# rtkSchematic.net
KiCad netlist of a schematic drawn in EAGLE
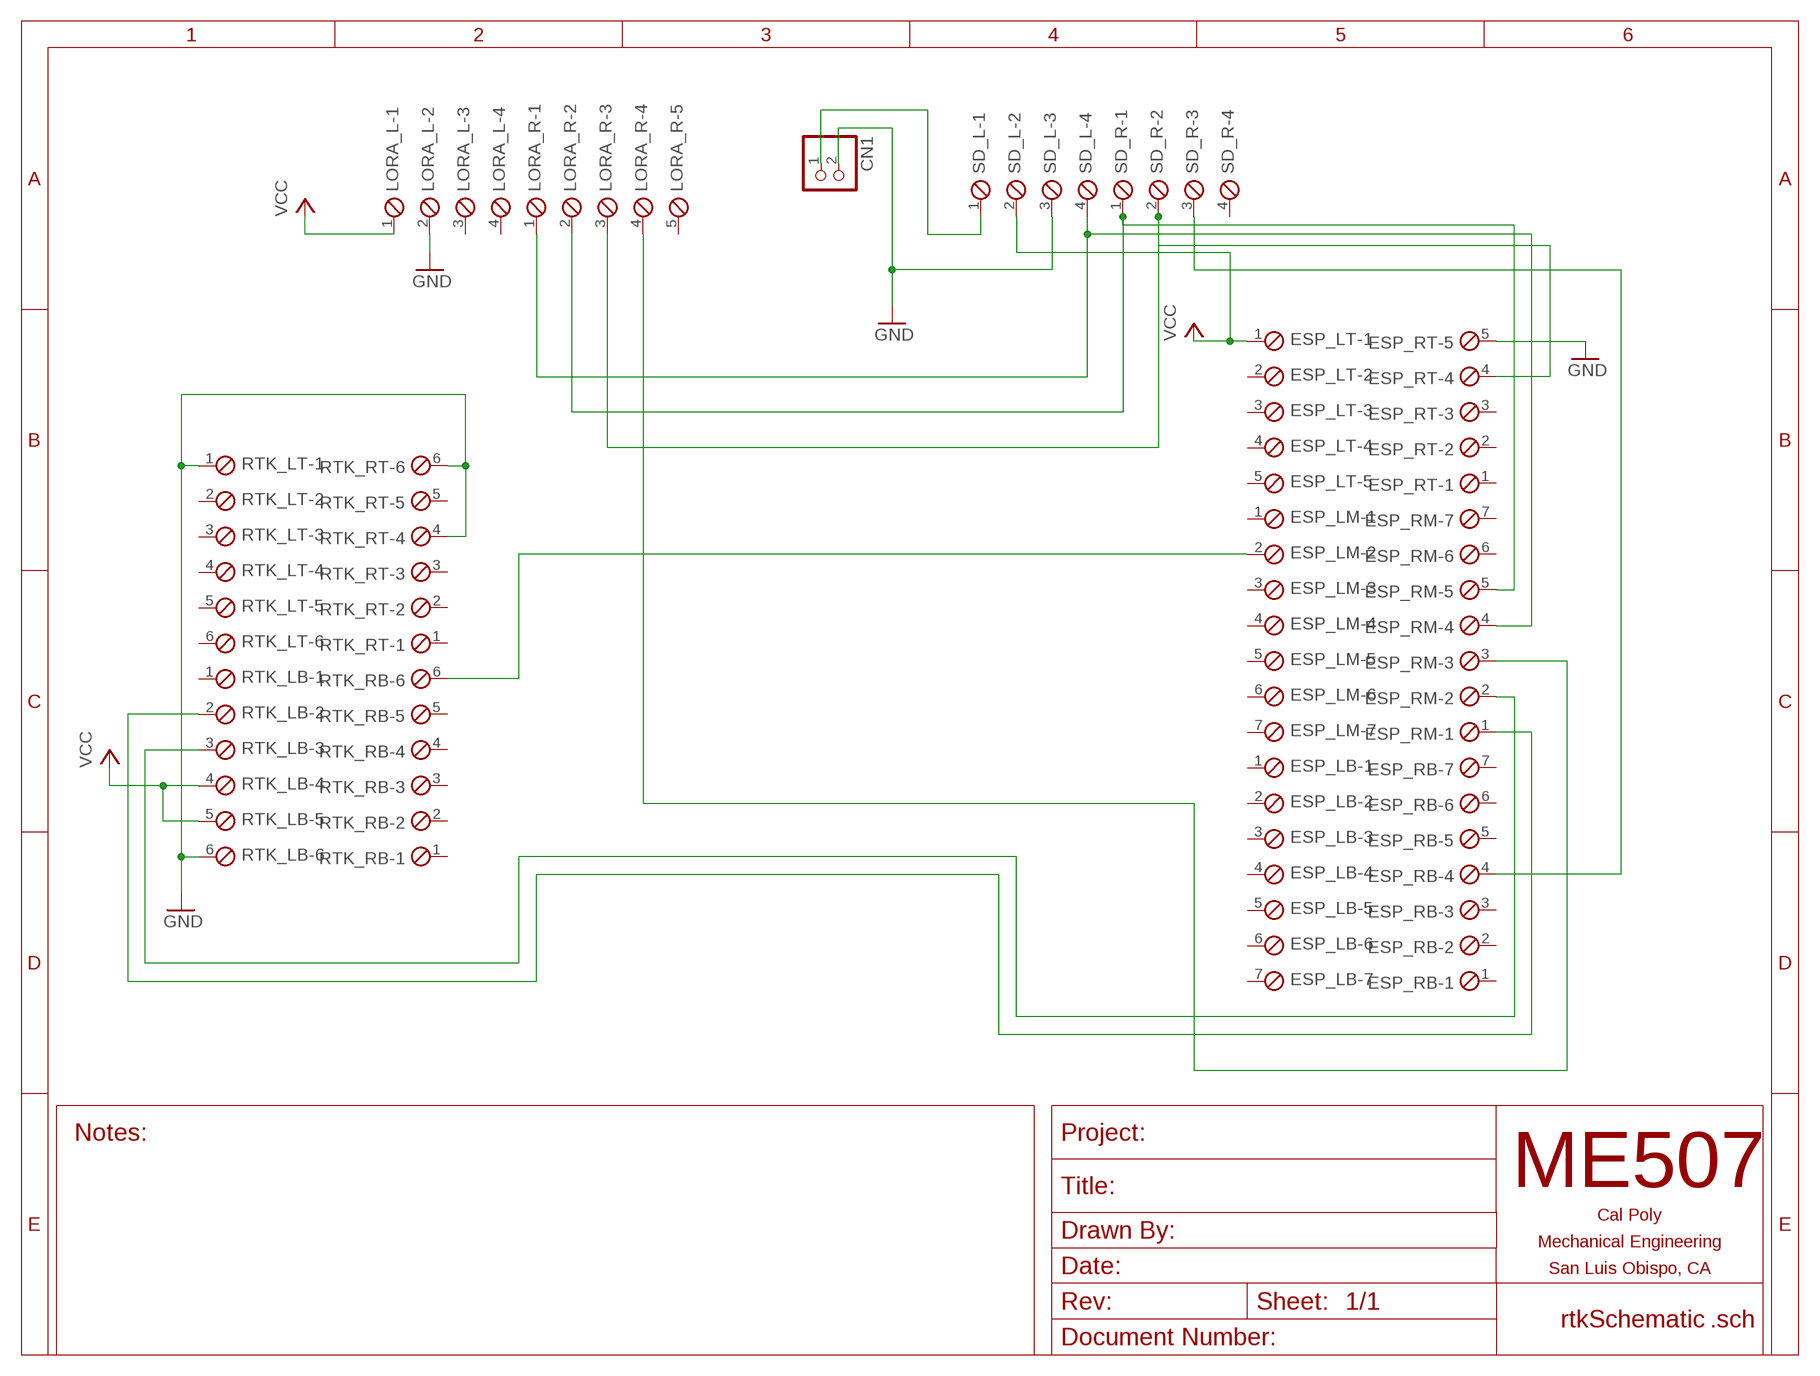
[diagram p0: schematic, sheet 1]

(export (version "E")
  (design (tool "Eeschema 10.0.6"))
  (components
    (comp (ref "CN1")
      (value "JST_2PIN-SMT-RA")
      (footprint "eagle-import:JST-PH-2-SMT-RA")
      (libsource (lib "eagle-import") (part "JST_2PIN-SMT-RA"))
    )
    (comp (ref "ESP_LB")
      (value "SCREWTERM_7P_254")
      (footprint "eagle-import:7POL254")
      (libsource (lib "eagle-import") (part "SCREWTERM_7P_254"))
    )
    (comp (ref "ESP_LM")
      (value "SCREWTERM_7P_254")
      (footprint "eagle-import:7POL254")
      (libsource (lib "eagle-import") (part "SCREWTERM_7P_254"))
    )
    (comp (ref "ESP_LT")
      (value "SCREWTERM_5P_254")
      (footprint "eagle-import:5POL254")
      (libsource (lib "eagle-import") (part "SCREWTERM_5P_254"))
    )
    (comp (ref "ESP_RB")
      (value "SCREWTERM_7P_254")
      (footprint "eagle-import:7POL254")
      (libsource (lib "eagle-import") (part "SCREWTERM_7P_254"))
    )
    (comp (ref "ESP_RM")
      (value "SCREWTERM_7P_254")
      (footprint "eagle-import:7POL254")
      (libsource (lib "eagle-import") (part "SCREWTERM_7P_254"))
    )
    (comp (ref "ESP_RT")
      (value "SCREWTERM_5P_254")
      (footprint "eagle-import:5POL254")
      (libsource (lib "eagle-import") (part "SCREWTERM_5P_254"))
    )
    (comp (ref "LORA_L")
      (value "SCREWTERM_4P_254")
      (footprint "eagle-import:4POL254")
      (libsource (lib "eagle-import") (part "SCREWTERM_4P_254"))
    )
    (comp (ref "LORA_R")
      (value "SCREWTERM_5P_254")
      (footprint "eagle-import:5POL254")
      (libsource (lib "eagle-import") (part "SCREWTERM_5P_254"))
    )
    (comp (ref "RTK_LB")
      (value "SCREWTERM_6P_254")
      (footprint "eagle-import:6POL254")
      (libsource (lib "eagle-import") (part "SCREWTERM_6P_254"))
    )
    (comp (ref "RTK_LT")
      (value "SCREWTERM_6P_254")
      (footprint "eagle-import:6POL254")
      (libsource (lib "eagle-import") (part "SCREWTERM_6P_254"))
    )
    (comp (ref "RTK_RB")
      (value "SCREWTERM_6P_254")
      (footprint "eagle-import:6POL254")
      (libsource (lib "eagle-import") (part "SCREWTERM_6P_254"))
    )
    (comp (ref "RTK_RT")
      (value "SCREWTERM_6P_254")
      (footprint "eagle-import:6POL254")
      (libsource (lib "eagle-import") (part "SCREWTERM_6P_254"))
    )
    (comp (ref "SD_L")
      (value "SCREWTERM_4P_254")
      (footprint "eagle-import:4POL254")
      (libsource (lib "eagle-import") (part "SCREWTERM_4P_254"))
    )
    (comp (ref "SD_R")
      (value "SCREWTERM_4P_254")
      (footprint "eagle-import:4POL254")
      (libsource (lib "eagle-import") (part "SCREWTERM_4P_254"))
    )
  )
  (nets
    (net (code "1") (name "GND") (class "Default")
      (node (ref "CN1") (pin "2") (pinfunction "1_2") (pintype "passive"))
      (node (ref "ESP_RT") (pin "5") (pinfunction "1_5") (pintype "passive"))
      (node (ref "LORA_L") (pin "2") (pinfunction "1_2") (pintype "passive"))
      (node (ref "RTK_LB") (pin "6") (pinfunction "1_6") (pintype "passive"))
      (node (ref "RTK_LT") (pin "1") (pinfunction "1_1") (pintype "passive"))
      (node (ref "RTK_RT") (pin "4") (pinfunction "1_4") (pintype "passive"))
      (node (ref "RTK_RT") (pin "6") (pinfunction "1_6") (pintype "passive"))
      (node (ref "SD_L") (pin "3") (pinfunction "1_3") (pintype "passive"))
    )
    (net (code "2") (name "Net-(CN1-2)") (class "Default")
      (node (ref "CN1") (pin "1") (pinfunction "2_1") (pintype "passive"))
      (node (ref "SD_L") (pin "1") (pinfunction "1_1") (pintype "passive"))
    )
    (net (code "3") (name "Net-(ESP_LMB-1)") (class "Default")
      (node (ref "ESP_LM") (pin "2") (pinfunction "1_2") (pintype "passive"))
      (node (ref "RTK_RB") (pin "6") (pinfunction "1_6") (pintype "passive"))
    )
    (net (code "4") (name "Net-(ESP_RBD-1)") (class "Default")
      (node (ref "ESP_RB") (pin "4") (pinfunction "1_4") (pintype "passive"))
      (node (ref "SD_R") (pin "3") (pinfunction "1_3") (pintype "passive"))
    )
    (net (code "5") (name "Net-(ESP_RMB-1)") (class "Default")
      (node (ref "ESP_RM") (pin "2") (pinfunction "1_2") (pintype "passive"))
      (node (ref "RTK_LB") (pin "3") (pinfunction "1_3") (pintype "passive"))
    )
    (net (code "6") (name "Net-(ESP_RMC-1)") (class "Default")
      (node (ref "ESP_RM") (pin "3") (pinfunction "1_3") (pintype "passive"))
      (node (ref "LORA_R") (pin "4") (pinfunction "1_4") (pintype "passive"))
    )
    (net (code "7") (name "Net-(ESP_RMD-1)") (class "Default")
      (node (ref "ESP_RM") (pin "4") (pinfunction "1_4") (pintype "passive"))
      (node (ref "LORA_R") (pin "1") (pinfunction "1_1") (pintype "passive"))
      (node (ref "SD_L") (pin "4") (pinfunction "1_4") (pintype "passive"))
    )
    (net (code "8") (name "Net-(ESP_RME-1)") (class "Default")
      (node (ref "ESP_RM") (pin "5") (pinfunction "1_5") (pintype "passive"))
      (node (ref "LORA_R") (pin "2") (pinfunction "1_2") (pintype "passive"))
      (node (ref "SD_R") (pin "1") (pinfunction "1_1") (pintype "passive"))
    )
    (net (code "9") (name "Net-(ESP_RTD-1)") (class "Default")
      (node (ref "ESP_RT") (pin "4") (pinfunction "1_4") (pintype "passive"))
      (node (ref "LORA_R") (pin "3") (pinfunction "1_3") (pintype "passive"))
      (node (ref "SD_R") (pin "2") (pinfunction "1_2") (pintype "passive"))
    )
    (net (code "10") (name "Net-(RTK_LBB-1)") (class "Default")
      (node (ref "ESP_RM") (pin "1") (pinfunction "1_1") (pintype "passive"))
      (node (ref "RTK_LB") (pin "2") (pinfunction "1_2") (pintype "passive"))
    )
    (net (code "11") (name "VCC") (class "Default")
      (node (ref "ESP_LT") (pin "1") (pinfunction "1_1") (pintype "passive"))
      (node (ref "LORA_L") (pin "1") (pinfunction "1_1") (pintype "passive"))
      (node (ref "RTK_LB") (pin "4") (pinfunction "1_4") (pintype "passive"))
      (node (ref "RTK_LB") (pin "5") (pinfunction "1_5") (pintype "passive"))
      (node (ref "SD_L") (pin "2") (pinfunction "1_2") (pintype "passive"))
    )
    (net (code "12") (name "unconnected-(ESP_LB-Pad1)") (class "Default")
      (node (ref "ESP_LB") (pin "1") (pinfunction "1_1") (pintype "passive"))
    )
    (net (code "13") (name "unconnected-(ESP_LBB-1-Pad2)") (class "Default")
      (node (ref "ESP_LB") (pin "2") (pinfunction "1_2") (pintype "passive"))
    )
    (net (code "14") (name "unconnected-(ESP_LBC-1-Pad3)") (class "Default")
      (node (ref "ESP_LB") (pin "3") (pinfunction "1_3") (pintype "passive"))
    )
    (net (code "15") (name "unconnected-(ESP_LBD-1-Pad4)") (class "Default")
      (node (ref "ESP_LB") (pin "4") (pinfunction "1_4") (pintype "passive"))
    )
    (net (code "16") (name "unconnected-(ESP_LBE-1-Pad5)") (class "Default")
      (node (ref "ESP_LB") (pin "5") (pinfunction "1_5") (pintype "passive"))
    )
    (net (code "17") (name "unconnected-(ESP_LBF-1-Pad6)") (class "Default")
      (node (ref "ESP_LB") (pin "6") (pinfunction "1_6") (pintype "passive"))
    )
    (net (code "18") (name "unconnected-(ESP_LBG-1-Pad7)") (class "Default")
      (node (ref "ESP_LB") (pin "7") (pinfunction "1_7") (pintype "passive"))
    )
    (net (code "19") (name "unconnected-(ESP_LM-Pad1)") (class "Default")
      (node (ref "ESP_LM") (pin "1") (pinfunction "1_1") (pintype "passive"))
    )
    (net (code "20") (name "unconnected-(ESP_LMC-1-Pad3)") (class "Default")
      (node (ref "ESP_LM") (pin "3") (pinfunction "1_3") (pintype "passive"))
    )
    (net (code "21") (name "unconnected-(ESP_LMD-1-Pad4)") (class "Default")
      (node (ref "ESP_LM") (pin "4") (pinfunction "1_4") (pintype "passive"))
    )
    (net (code "22") (name "unconnected-(ESP_LME-1-Pad5)") (class "Default")
      (node (ref "ESP_LM") (pin "5") (pinfunction "1_5") (pintype "passive"))
    )
    (net (code "23") (name "unconnected-(ESP_LMF-1-Pad6)") (class "Default")
      (node (ref "ESP_LM") (pin "6") (pinfunction "1_6") (pintype "passive"))
    )
    (net (code "24") (name "unconnected-(ESP_LMG-1-Pad7)") (class "Default")
      (node (ref "ESP_LM") (pin "7") (pinfunction "1_7") (pintype "passive"))
    )
    (net (code "25") (name "unconnected-(ESP_LTB-1-Pad2)") (class "Default")
      (node (ref "ESP_LT") (pin "2") (pinfunction "1_2") (pintype "passive"))
    )
    (net (code "26") (name "unconnected-(ESP_LTC-1-Pad3)") (class "Default")
      (node (ref "ESP_LT") (pin "3") (pinfunction "1_3") (pintype "passive"))
    )
    (net (code "27") (name "unconnected-(ESP_LTD-1-Pad4)") (class "Default")
      (node (ref "ESP_LT") (pin "4") (pinfunction "1_4") (pintype "passive"))
    )
    (net (code "28") (name "unconnected-(ESP_LTE-1-Pad5)") (class "Default")
      (node (ref "ESP_LT") (pin "5") (pinfunction "1_5") (pintype "passive"))
    )
    (net (code "29") (name "unconnected-(ESP_RB-Pad1)") (class "Default")
      (node (ref "ESP_RB") (pin "1") (pinfunction "1_1") (pintype "passive"))
    )
    (net (code "30") (name "unconnected-(ESP_RBB-1-Pad2)") (class "Default")
      (node (ref "ESP_RB") (pin "2") (pinfunction "1_2") (pintype "passive"))
    )
    (net (code "31") (name "unconnected-(ESP_RBC-1-Pad3)") (class "Default")
      (node (ref "ESP_RB") (pin "3") (pinfunction "1_3") (pintype "passive"))
    )
    (net (code "32") (name "unconnected-(ESP_RBE-1-Pad5)") (class "Default")
      (node (ref "ESP_RB") (pin "5") (pinfunction "1_5") (pintype "passive"))
    )
    (net (code "33") (name "unconnected-(ESP_RBF-1-Pad6)") (class "Default")
      (node (ref "ESP_RB") (pin "6") (pinfunction "1_6") (pintype "passive"))
    )
    (net (code "34") (name "unconnected-(ESP_RBG-1-Pad7)") (class "Default")
      (node (ref "ESP_RB") (pin "7") (pinfunction "1_7") (pintype "passive"))
    )
    (net (code "35") (name "unconnected-(ESP_RMF-1-Pad6)") (class "Default")
      (node (ref "ESP_RM") (pin "6") (pinfunction "1_6") (pintype "passive"))
    )
    (net (code "36") (name "unconnected-(ESP_RMG-1-Pad7)") (class "Default")
      (node (ref "ESP_RM") (pin "7") (pinfunction "1_7") (pintype "passive"))
    )
    (net (code "37") (name "unconnected-(ESP_RT-Pad1)") (class "Default")
      (node (ref "ESP_RT") (pin "1") (pinfunction "1_1") (pintype "passive"))
    )
    (net (code "38") (name "unconnected-(ESP_RTB-1-Pad2)") (class "Default")
      (node (ref "ESP_RT") (pin "2") (pinfunction "1_2") (pintype "passive"))
    )
    (net (code "39") (name "unconnected-(ESP_RTC-1-Pad3)") (class "Default")
      (node (ref "ESP_RT") (pin "3") (pinfunction "1_3") (pintype "passive"))
    )
    (net (code "40") (name "unconnected-(LORA_LC-1-Pad3)") (class "Default")
      (node (ref "LORA_L") (pin "3") (pinfunction "1_3") (pintype "passive"))
    )
    (net (code "41") (name "unconnected-(LORA_LD-1-Pad4)") (class "Default")
      (node (ref "LORA_L") (pin "4") (pinfunction "1_4") (pintype "passive"))
    )
    (net (code "42") (name "unconnected-(LORA_RE-1-Pad5)") (class "Default")
      (node (ref "LORA_R") (pin "5") (pinfunction "1_5") (pintype "passive"))
    )
    (net (code "43") (name "unconnected-(RTK_LB-Pad1)") (class "Default")
      (node (ref "RTK_LB") (pin "1") (pinfunction "1_1") (pintype "passive"))
    )
    (net (code "44") (name "unconnected-(RTK_LTB-1-Pad2)") (class "Default")
      (node (ref "RTK_LT") (pin "2") (pinfunction "1_2") (pintype "passive"))
    )
    (net (code "45") (name "unconnected-(RTK_LTC-1-Pad3)") (class "Default")
      (node (ref "RTK_LT") (pin "3") (pinfunction "1_3") (pintype "passive"))
    )
    (net (code "46") (name "unconnected-(RTK_LTD-1-Pad4)") (class "Default")
      (node (ref "RTK_LT") (pin "4") (pinfunction "1_4") (pintype "passive"))
    )
    (net (code "47") (name "unconnected-(RTK_LTE-1-Pad5)") (class "Default")
      (node (ref "RTK_LT") (pin "5") (pinfunction "1_5") (pintype "passive"))
    )
    (net (code "48") (name "unconnected-(RTK_LTF-1-Pad6)") (class "Default")
      (node (ref "RTK_LT") (pin "6") (pinfunction "1_6") (pintype "passive"))
    )
    (net (code "49") (name "unconnected-(RTK_RB-Pad1)") (class "Default")
      (node (ref "RTK_RB") (pin "1") (pinfunction "1_1") (pintype "passive"))
    )
    (net (code "50") (name "unconnected-(RTK_RBB-1-Pad2)") (class "Default")
      (node (ref "RTK_RB") (pin "2") (pinfunction "1_2") (pintype "passive"))
    )
    (net (code "51") (name "unconnected-(RTK_RBC-1-Pad3)") (class "Default")
      (node (ref "RTK_RB") (pin "3") (pinfunction "1_3") (pintype "passive"))
    )
    (net (code "52") (name "unconnected-(RTK_RBD-1-Pad4)") (class "Default")
      (node (ref "RTK_RB") (pin "4") (pinfunction "1_4") (pintype "passive"))
    )
    (net (code "53") (name "unconnected-(RTK_RBE-1-Pad5)") (class "Default")
      (node (ref "RTK_RB") (pin "5") (pinfunction "1_5") (pintype "passive"))
    )
    (net (code "54") (name "unconnected-(RTK_RT-Pad1)") (class "Default")
      (node (ref "RTK_RT") (pin "1") (pinfunction "1_1") (pintype "passive"))
    )
    (net (code "55") (name "unconnected-(RTK_RTB-1-Pad2)") (class "Default")
      (node (ref "RTK_RT") (pin "2") (pinfunction "1_2") (pintype "passive"))
    )
    (net (code "56") (name "unconnected-(RTK_RTC-1-Pad3)") (class "Default")
      (node (ref "RTK_RT") (pin "3") (pinfunction "1_3") (pintype "passive"))
    )
    (net (code "57") (name "unconnected-(RTK_RTE-1-Pad5)") (class "Default")
      (node (ref "RTK_RT") (pin "5") (pinfunction "1_5") (pintype "passive"))
    )
    (net (code "58") (name "unconnected-(SD_RD-1-Pad4)") (class "Default")
      (node (ref "SD_R") (pin "4") (pinfunction "1_4") (pintype "passive"))
    )
  )
)
